# BBB_Headers.net
KiCad netlist of a schematic drawn in Altium Designer
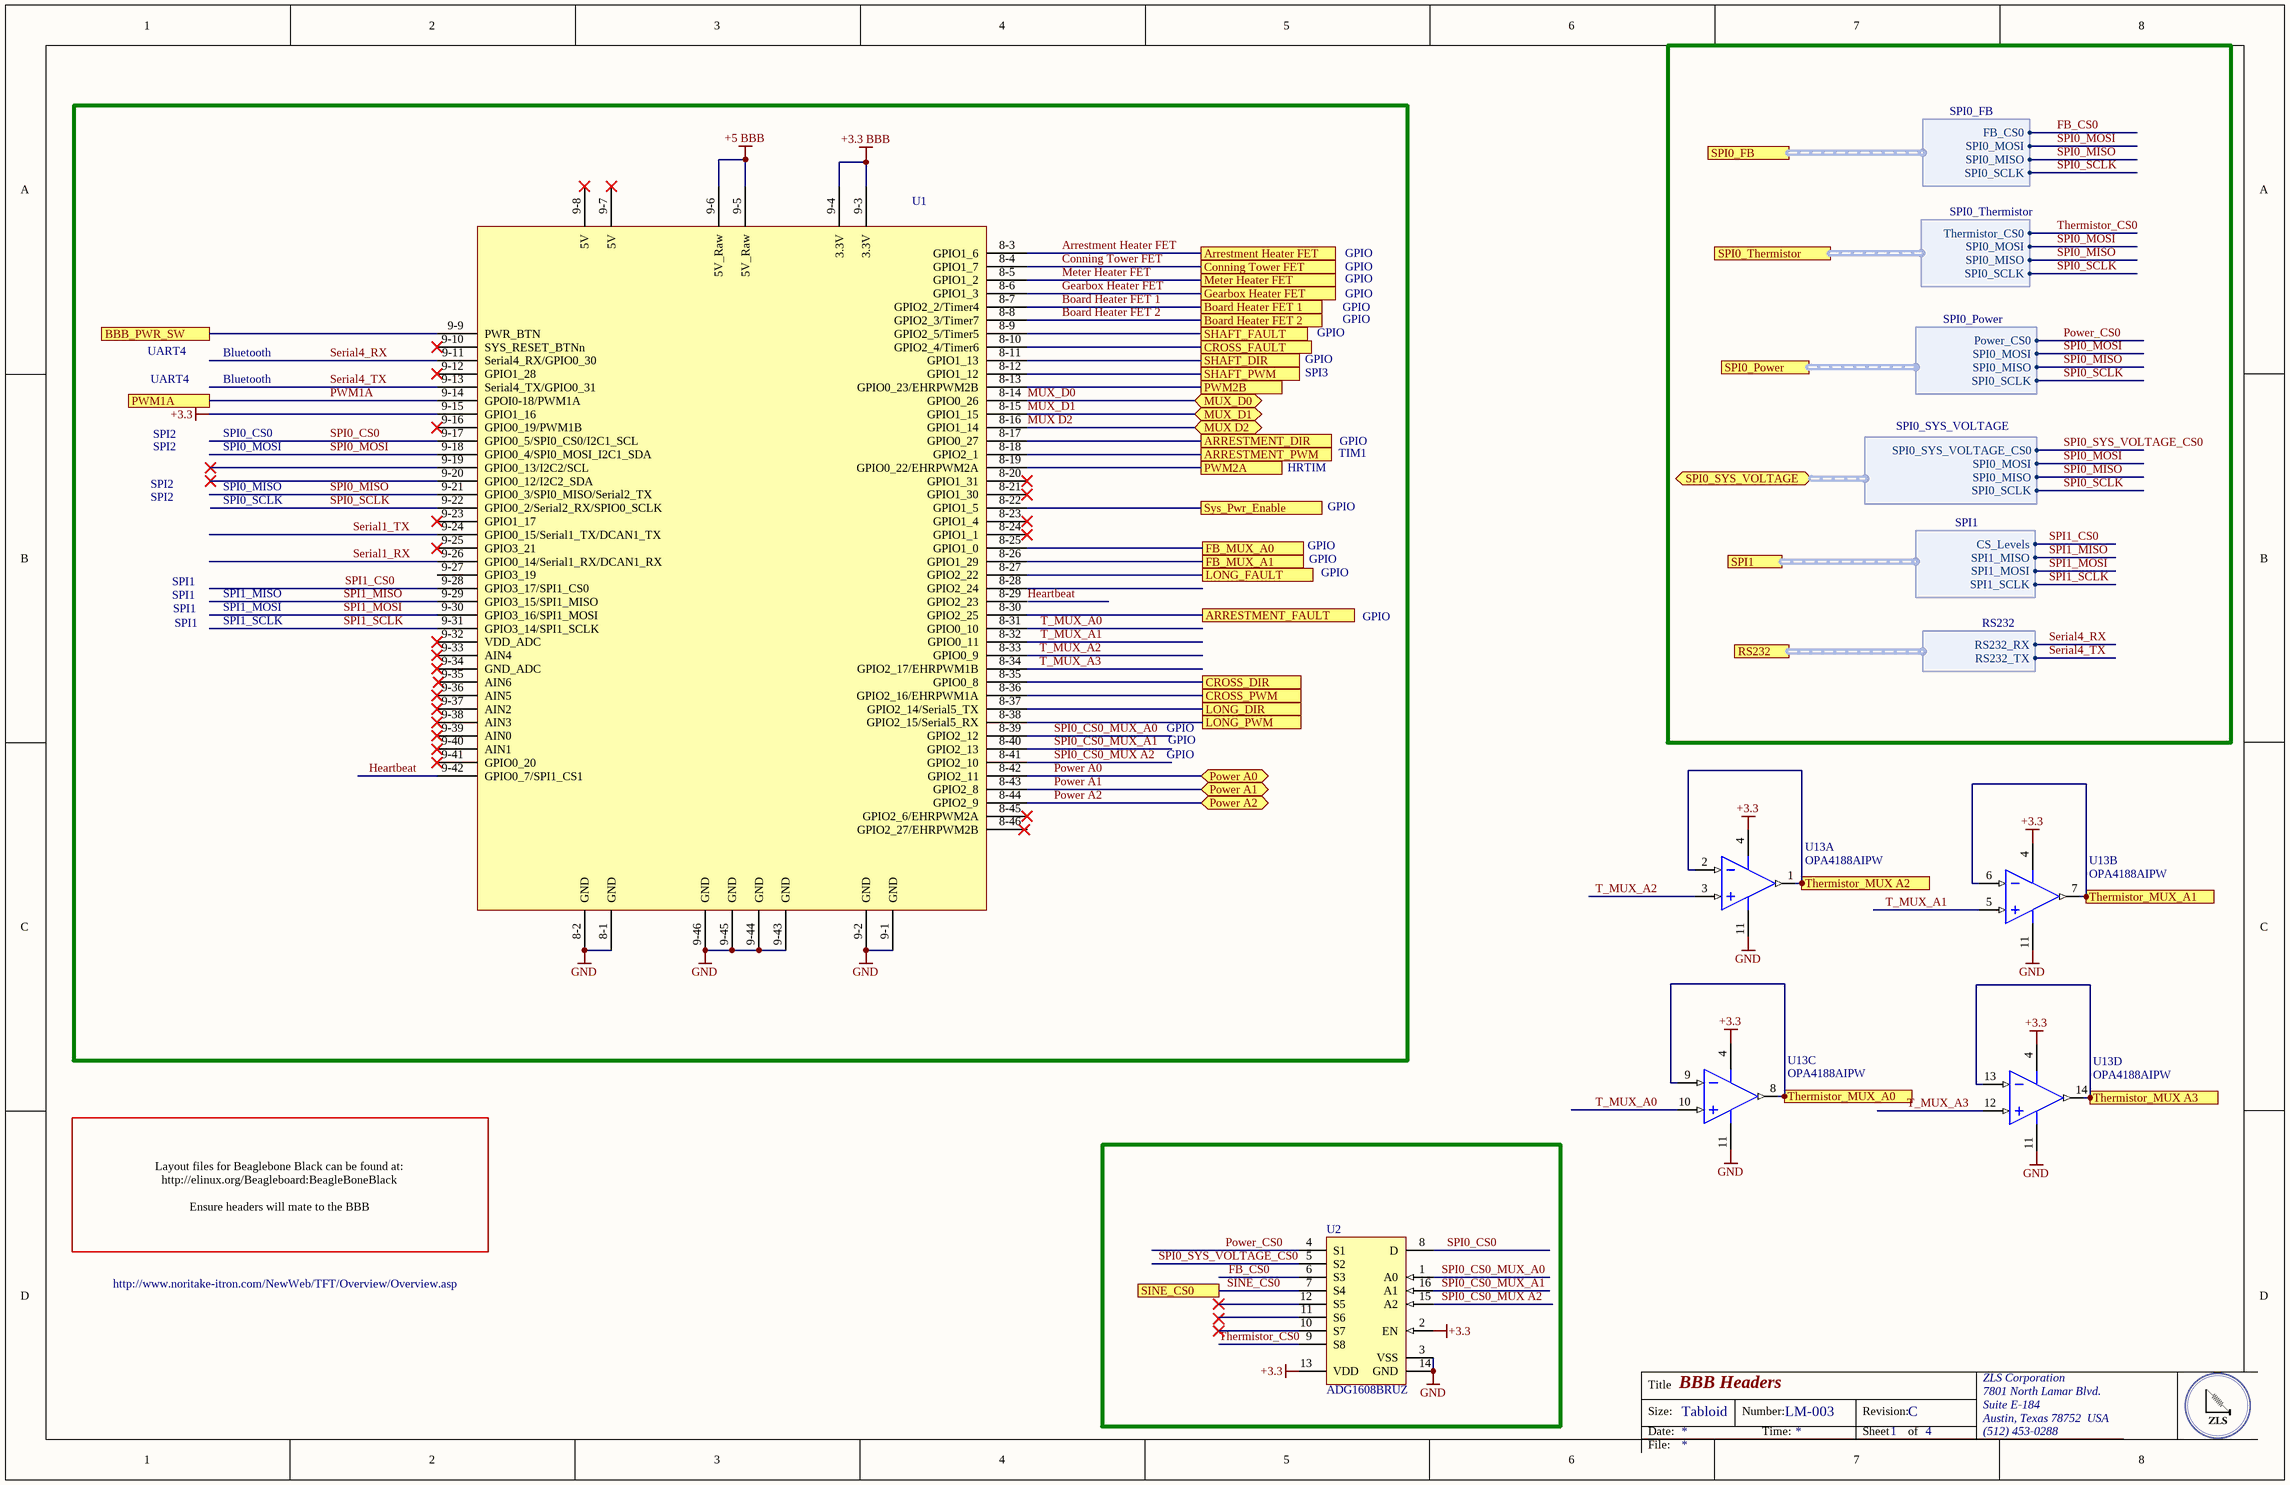
[diagram p0: BBB Headers.SchDoc]

(export (version "E")
  (design (tool "Eeschema 10.0.6"))
  (components
    (comp (ref "U1")
      (value "BBB Header x 2")
      (footprint "Beaglebone Black Thru")
      (description "Beaglebone Black Header")
      (fields
        (field (name "MANUFACTURER") "Samtec Inc.")
        (field (name "MANUFACTURER PART NUMBER") "SSW-123-03-G-D")
      )
      (libsource (lib "ZLS_Schematic_lib") (part "Beaglebone_Black"))
    )
    (comp (ref "U2")
      (value "ADG1608BRUZ")
      (footprint "ADI-RU-16_M")
      (description "4.5 Ohm Ron, 8-Channel +/-5 V,+12 V, +5 V and +3.3 V Multiplexer, 16-pin SOP (RU-16), Tube")
      (fields (field (name "MANUFACTURER") "Analog Devices Inc.") (field (name "BASE PART NUMBER") "ADG1608"))
      (libsource (lib "Altium Content Vault") (part "CMP-0793-00136-1"))
    )
    (comp (ref "U13")
      (value "OPA4188AIPW")
      (footprint "PW0014A_N")
      (fields (field (name "MANUFACTURER") "Texas Instruments"))
      (libsource (lib "Altium Content Vault") (part "TI-OPA4188-PW14"))
    )
  )
  (nets
    (net (code "7") (name "+3.3") (class "Default")
      (node (ref "U1") (pin "9-15") (pinfunction "GPIO1_16_9-15") (pintype "passive"))
      (node (ref "U13") (pin "4") (pinfunction "V+_4") (pintype "power_in"))
      (node (ref "U2") (pin "13") (pinfunction "VDD_13") (pintype "power_in"))
      (node (ref "U2") (pin "2") (pinfunction "EN_2") (pintype "input"))
    )
    (net (code "8") (name "+3.3 BBB") (class "Default")
      (node (ref "U1") (pin "9-3") (pinfunction "3.3V_9-3") (pintype "passive"))
      (node (ref "U1") (pin "9-4") (pinfunction "3.3V_9-4") (pintype "passive"))
    )
    (net (code "9") (name "+5 BBB") (class "Default")
      (node (ref "U1") (pin "9-5") (pinfunction "5V_Raw_9-5") (pintype "passive"))
      (node (ref "U1") (pin "9-6") (pinfunction "5V_Raw_9-6") (pintype "passive"))
    )
    (net (code "10") (name "/ARRESTMENT_DIR") (class "Default")
      (node (ref "U1") (pin "8-17") (pinfunction "GPIO0_27_8-17") (pintype "passive"))
    )
    (net (code "11") (name "/ARRESTMENT_FAULT") (class "Default")
      (node (ref "U1") (pin "8-30") (pinfunction "GPIO2_25_8-30") (pintype "passive"))
    )
    (net (code "12") (name "/ARRESTMENT_PWM") (class "Default")
      (node (ref "U1") (pin "8-18") (pinfunction "GPIO2_1_8-18") (pintype "passive"))
    )
    (net (code "13") (name "/Arrestment Heater FET") (class "Default")
      (node (ref "U1") (pin "8-3") (pinfunction "GPIO1_6_8-3") (pintype "passive"))
    )
    (net (code "14") (name "/BBB_PWR_SW") (class "Default")
      (node (ref "U1") (pin "9-9") (pinfunction "PWR_BTN_9-9") (pintype "passive"))
    )
    (net (code "15") (name "/Board Heater FET 1") (class "Default")
      (node (ref "U1") (pin "8-7") (pinfunction "GPIO2_2/Timer4_8-7") (pintype "passive"))
    )
    (net (code "16") (name "/Board Heater FET 2") (class "Default")
      (node (ref "U1") (pin "8-8") (pinfunction "GPIO2_3/Timer7_8-8") (pintype "passive"))
    )
    (net (code "17") (name "/CROSS_DIR") (class "Default")
      (node (ref "U1") (pin "8-35") (pinfunction "GPIO0_8_8-35") (pintype "passive"))
    )
    (net (code "18") (name "/CROSS_FAULT") (class "Default")
      (node (ref "U1") (pin "8-10") (pinfunction "GPIO2_4/Timer6_8-10") (pintype "passive"))
    )
    (net (code "19") (name "/CROSS_PWM") (class "Default")
      (node (ref "U1") (pin "8-36") (pinfunction "GPIO2_16/EHRPWM1A_8-36") (pintype "passive"))
    )
    (net (code "20") (name "/Conning Tower FET") (class "Default")
      (node (ref "U1") (pin "8-4") (pinfunction "GPIO1_7_8-4") (pintype "passive"))
    )
    (net (code "21") (name "/FB_CS0") (class "Default")
      (node (ref "U2") (pin "6") (pinfunction "S3_6") (pintype "passive"))
    )
    (net (code "22") (name "/FB_MUX_A0") (class "Default")
      (node (ref "U1") (pin "8-25") (pinfunction "GPIO1_0_8-25") (pintype "passive"))
    )
    (net (code "23") (name "/FB_MUX_A1") (class "Default")
      (node (ref "U1") (pin "8-26") (pinfunction "GPIO1_29_8-26") (pintype "passive"))
    )
    (net (code "24") (name "/Gearbox Heater FET") (class "Default")
      (node (ref "U1") (pin "8-6") (pinfunction "GPIO1_3_8-6") (pintype "passive"))
    )
    (net (code "25") (name "/Heartbeat") (class "Default")
      (node (ref "U1") (pin "8-29") (pinfunction "GPIO2_23_8-29") (pintype "passive"))
      (node (ref "U1") (pin "9-42") (pinfunction "GPIO0_7/SPI1_CS1_9-42") (pintype "passive"))
    )
    (net (code "26") (name "/LONG_DIR") (class "Default")
      (node (ref "U1") (pin "8-37") (pinfunction "GPIO2_14/Serial5_TX_8-37") (pintype "passive"))
    )
    (net (code "27") (name "/LONG_FAULT") (class "Default")
      (node (ref "U1") (pin "8-27") (pinfunction "GPIO2_22_8-27") (pintype "passive"))
    )
    (net (code "28") (name "/LONG_PWM") (class "Default")
      (node (ref "U1") (pin "8-38") (pinfunction "GPIO2_15/Serial5_RX_8-38") (pintype "passive"))
    )
    (net (code "29") (name "/MUX D2") (class "Default")
      (node (ref "U1") (pin "8-16") (pinfunction "GPIO1_14_8-16") (pintype "passive"))
    )
    (net (code "30") (name "/MUX_D0") (class "Default")
      (node (ref "U1") (pin "8-14") (pinfunction "GPIO0_26_8-14") (pintype "passive"))
    )
    (net (code "31") (name "/MUX_D1") (class "Default")
      (node (ref "U1") (pin "8-15") (pinfunction "GPIO1_15_8-15") (pintype "passive"))
    )
    (net (code "32") (name "/Meter Heater FET") (class "Default")
      (node (ref "U1") (pin "8-5") (pinfunction "GPIO1_2_8-5") (pintype "passive"))
    )
    (net (code "33") (name "/PWM1A") (class "Default")
      (node (ref "U1") (pin "9-14") (pinfunction "GPOI0-18/PWM1A_9-14") (pintype "passive"))
    )
    (net (code "34") (name "/PWM2A") (class "Default")
      (node (ref "U1") (pin "8-19") (pinfunction "GPIO0_22/EHRPWM2A_8-19") (pintype "passive"))
    )
    (net (code "35") (name "/PWM2B") (class "Default")
      (node (ref "U1") (pin "8-13") (pinfunction "GPIO0_23/EHRPWM2B_8-13") (pintype "passive"))
    )
    (net (code "36") (name "/Power A0") (class "Default")
      (node (ref "U1") (pin "8-42") (pinfunction "GPIO2_11_8-42") (pintype "passive"))
    )
    (net (code "37") (name "/Power A1") (class "Default")
      (node (ref "U1") (pin "8-43") (pinfunction "GPIO2_8_8-43") (pintype "passive"))
    )
    (net (code "38") (name "/Power A2") (class "Default")
      (node (ref "U1") (pin "8-44") (pinfunction "GPIO2_9_8-44") (pintype "passive"))
    )
    (net (code "39") (name "/Power_CS0") (class "Default")
      (node (ref "U2") (pin "4") (pinfunction "S1_4") (pintype "passive"))
    )
    (net (code "40") (name "/SHAFT_DIR") (class "Default")
      (node (ref "U1") (pin "8-11") (pinfunction "GPIO1_13_8-11") (pintype "passive"))
    )
    (net (code "41") (name "/SHAFT_FAULT") (class "Default")
      (node (ref "U1") (pin "8-9") (pinfunction "GPIO2_5/Timer5_8-9") (pintype "passive"))
    )
    (net (code "42") (name "/SHAFT_PWM") (class "Default")
      (node (ref "U1") (pin "8-12") (pinfunction "GPIO1_12_8-12") (pintype "passive"))
    )
    (net (code "43") (name "/SINE_CS0") (class "Default")
      (node (ref "U2") (pin "7") (pinfunction "S4_7") (pintype "passive"))
    )
    (net (code "44") (name "/SPI0_CS0") (class "Default")
      (node (ref "U1") (pin "9-17") (pinfunction "GPIO0_5/SPI0_CS0/I2C1_SCL_9-17") (pintype "passive"))
      (node (ref "U2") (pin "8") (pinfunction "D_8") (pintype "passive"))
    )
    (net (code "45") (name "/SPI0_CS0_MUX A2") (class "Default")
      (node (ref "U1") (pin "8-41") (pinfunction "GPIO2_10_8-41") (pintype "passive"))
      (node (ref "U2") (pin "15") (pinfunction "A2_15") (pintype "input"))
    )
    (net (code "46") (name "/SPI0_CS0_MUX_A0") (class "Default")
      (node (ref "U1") (pin "8-39") (pinfunction "GPIO2_12_8-39") (pintype "passive"))
      (node (ref "U2") (pin "1") (pinfunction "A0_1") (pintype "input"))
    )
    (net (code "47") (name "/SPI0_CS0_MUX_A1") (class "Default")
      (node (ref "U1") (pin "8-40") (pinfunction "GPIO2_13_8-40") (pintype "passive"))
      (node (ref "U2") (pin "16") (pinfunction "A1_16") (pintype "input"))
    )
    (net (code "48") (name "/SPI0_MISO") (class "Default")
      (node (ref "U1") (pin "9-21") (pinfunction "GPIO0_3/SPI0_MISO/Serial2_TX_9-21") (pintype "passive"))
    )
    (net (code "49") (name "/SPI0_MOSI") (class "Default")
      (node (ref "U1") (pin "9-18") (pinfunction "GPIO0_4/SPI0_MOSI_I2C1_SDA_9-18") (pintype "passive"))
    )
    (net (code "50") (name "/SPI0_SCLK") (class "Default")
      (node (ref "U1") (pin "9-22") (pinfunction "GPIO0_2/Serial2_RX/SPIO0_SCLK_9-22") (pintype "passive"))
    )
    (net (code "51") (name "/SPI0_SYS_VOLTAGE_CS0") (class "Default")
      (node (ref "U2") (pin "5") (pinfunction "S2_5") (pintype "passive"))
    )
    (net (code "52") (name "/SPI1_CS0") (class "Default")
      (node (ref "U1") (pin "9-28") (pinfunction "GPIO3_17/SPI1_CS0_9-28") (pintype "passive"))
    )
    (net (code "53") (name "/SPI1_MISO") (class "Default")
      (node (ref "U1") (pin "9-29") (pinfunction "GPIO3_15/SPI1_MISO_9-29") (pintype "passive"))
    )
    (net (code "54") (name "/SPI1_MOSI") (class "Default")
      (node (ref "U1") (pin "9-30") (pinfunction "GPIO3_16/SPI1_MOSI_9-30") (pintype "passive"))
    )
    (net (code "55") (name "/SPI1_SCLK") (class "Default")
      (node (ref "U1") (pin "9-31") (pinfunction "GPIO3_14/SPI1_SCLK_9-31") (pintype "passive"))
    )
    (net (code "56") (name "/Serial1_RX") (class "Default")
      (node (ref "U1") (pin "9-26") (pinfunction "GPIO0_14/Serial1_RX/DCAN1_RX_9-26") (pintype "passive"))
    )
    (net (code "57") (name "/Serial1_TX") (class "Default")
      (node (ref "U1") (pin "9-24") (pinfunction "GPIO0_15/Serial1_TX/DCAN1_TX_9-24") (pintype "passive"))
    )
    (net (code "58") (name "/Serial4_RX") (class "Default")
      (node (ref "U1") (pin "9-11") (pinfunction "Serial4_RX/GPIO0_30_9-11") (pintype "passive"))
    )
    (net (code "59") (name "/Serial4_TX") (class "Default")
      (node (ref "U1") (pin "9-13") (pinfunction "Serial4_TX/GPIO0_31_9-13") (pintype "passive"))
    )
    (net (code "60") (name "/Sys_Pwr_Enable") (class "Default")
      (node (ref "U1") (pin "8-22") (pinfunction "GPIO1_5_8-22") (pintype "passive"))
    )
    (net (code "61") (name "/T_MUX_A0") (class "Default")
      (node (ref "U1") (pin "8-31") (pinfunction "GPIO0_10_8-31") (pintype "passive"))
      (node (ref "U13") (pin "10") (pinfunction "IN_C+_10") (pintype "input"))
    )
    (net (code "62") (name "/T_MUX_A1") (class "Default")
      (node (ref "U1") (pin "8-32") (pinfunction "GPIO0_11_8-32") (pintype "passive"))
      (node (ref "U13") (pin "5") (pinfunction "IN_B+_5") (pintype "input"))
    )
    (net (code "63") (name "/T_MUX_A2") (class "Default")
      (node (ref "U1") (pin "8-33") (pinfunction "GPIO0_9_8-33") (pintype "passive"))
      (node (ref "U13") (pin "3") (pinfunction "IN_A+_3") (pintype "input"))
    )
    (net (code "64") (name "/T_MUX_A3") (class "Default")
      (node (ref "U1") (pin "8-34") (pinfunction "GPIO2_17/EHRPWM1B_8-34") (pintype "passive"))
      (node (ref "U13") (pin "12") (pinfunction "IN_D+_12") (pintype "input"))
    )
    (net (code "65") (name "/Thermistor_CS0") (class "Default")
      (node (ref "U2") (pin "9") (pinfunction "S8_9") (pintype "passive"))
    )
    (net (code "66") (name "/Thermistor_MUX A2") (class "Default")
      (node (ref "U13") (pin "1") (pinfunction "OUT_A_1") (pintype "output"))
      (node (ref "U13") (pin "2") (pinfunction "IN_A-_2") (pintype "input"))
    )
    (net (code "67") (name "/Thermistor_MUX A3") (class "Default")
      (node (ref "U13") (pin "13") (pinfunction "IN_D-_13") (pintype "input"))
      (node (ref "U13") (pin "14") (pinfunction "OUT_D_14") (pintype "output"))
    )
    (net (code "68") (name "/Thermistor_MUX_A0") (class "Default")
      (node (ref "U13") (pin "8") (pinfunction "OUT_C_8") (pintype "output"))
      (node (ref "U13") (pin "9") (pinfunction "IN_C-_9") (pintype "input"))
    )
    (net (code "69") (name "/Thermistor_MUX_A1") (class "Default")
      (node (ref "U13") (pin "6") (pinfunction "IN_B-_6") (pintype "input"))
      (node (ref "U13") (pin "7") (pinfunction "OUT_B_7") (pintype "output"))
    )
    (net (code "76") (name "GND") (class "Default")
      (node (ref "U1") (pin "8-1") (pinfunction "GND_8-1") (pintype "passive"))
      (node (ref "U1") (pin "8-2") (pinfunction "GND_8-2") (pintype "passive"))
      (node (ref "U1") (pin "9-1") (pinfunction "GND_9-1") (pintype "passive"))
      (node (ref "U1") (pin "9-2") (pinfunction "GND_9-2") (pintype "passive"))
      (node (ref "U1") (pin "9-43") (pinfunction "GND_9-43") (pintype "passive"))
      (node (ref "U1") (pin "9-44") (pinfunction "GND_9-44") (pintype "passive"))
      (node (ref "U1") (pin "9-45") (pinfunction "GND_9-45") (pintype "passive"))
      (node (ref "U1") (pin "9-46") (pinfunction "GND_9-46") (pintype "passive"))
      (node (ref "U13") (pin "11") (pinfunction "V-_11") (pintype "power_in"))
      (node (ref "U2") (pin "14") (pinfunction "GND_14") (pintype "power_in"))
      (node (ref "U2") (pin "3") (pinfunction "VSS_3") (pintype "power_in"))
    )
    (net (code "77") (name "unconnected-(U1-5V-Pad9-7)") (class "Default")
      (node (ref "U1") (pin "9-7") (pinfunction "5V_9-7") (pintype "passive+no_connect"))
    )
    (net (code "78") (name "unconnected-(U1-5V-Pad9-8)") (class "Default")
      (node (ref "U1") (pin "9-8") (pinfunction "5V_9-8") (pintype "passive+no_connect"))
    )
    (net (code "79") (name "unconnected-(U1-AIN0-Pad9-39)") (class "Default")
      (node (ref "U1") (pin "9-39") (pinfunction "AIN0_9-39") (pintype "passive+no_connect"))
    )
    (net (code "80") (name "unconnected-(U1-AIN1-Pad9-40)") (class "Default")
      (node (ref "U1") (pin "9-40") (pinfunction "AIN1_9-40") (pintype "passive+no_connect"))
    )
    (net (code "81") (name "unconnected-(U1-AIN2-Pad9-37)") (class "Default")
      (node (ref "U1") (pin "9-37") (pinfunction "AIN2_9-37") (pintype "passive+no_connect"))
    )
    (net (code "82") (name "unconnected-(U1-AIN3-Pad9-38)") (class "Default")
      (node (ref "U1") (pin "9-38") (pinfunction "AIN3_9-38") (pintype "passive+no_connect"))
    )
    (net (code "83") (name "unconnected-(U1-AIN4-Pad9-33)") (class "Default")
      (node (ref "U1") (pin "9-33") (pinfunction "AIN4_9-33") (pintype "passive+no_connect"))
    )
    (net (code "84") (name "unconnected-(U1-AIN5-Pad9-36)") (class "Default")
      (node (ref "U1") (pin "9-36") (pinfunction "AIN5_9-36") (pintype "passive+no_connect"))
    )
    (net (code "85") (name "unconnected-(U1-AIN6-Pad9-35)") (class "Default")
      (node (ref "U1") (pin "9-35") (pinfunction "AIN6_9-35") (pintype "passive"))
    )
    (net (code "86") (name "unconnected-(U1-GND_ADC-Pad9-34)") (class "Default")
      (node (ref "U1") (pin "9-34") (pinfunction "GND_ADC_9-34") (pintype "passive+no_connect"))
    )
    (net (code "87") (name "unconnected-(U1-GPIO0_12{slash}I2C2_SDA-Pad9-20)") (class "Default")
      (node (ref "U1") (pin "9-20") (pinfunction "GPIO0_12/I2C2_SDA_9-20") (pintype "passive+no_connect"))
    )
    (net (code "88") (name "unconnected-(U1-GPIO0_13{slash}I2C2{slash}SCL-Pad9-19)") (class "Default")
      (node (ref "U1") (pin "9-19") (pinfunction "GPIO0_13/I2C2/SCL_9-19") (pintype "passive+no_connect"))
    )
    (net (code "89") (name "unconnected-(U1-GPIO0_19{slash}PWM1B-Pad9-16)") (class "Default")
      (node (ref "U1") (pin "9-16") (pinfunction "GPIO0_19/PWM1B_9-16") (pintype "passive+no_connect"))
    )
    (net (code "90") (name "unconnected-(U1-GPIO0_20-Pad9-41)") (class "Default")
      (node (ref "U1") (pin "9-41") (pinfunction "GPIO0_20_9-41") (pintype "passive+no_connect"))
    )
    (net (code "91") (name "unconnected-(U1-GPIO1_1-Pad8-24)") (class "Default")
      (node (ref "U1") (pin "8-24") (pinfunction "GPIO1_1_8-24") (pintype "passive+no_connect"))
    )
    (net (code "92") (name "unconnected-(U1-GPIO1_4-Pad8-23)") (class "Default")
      (node (ref "U1") (pin "8-23") (pinfunction "GPIO1_4_8-23") (pintype "passive+no_connect"))
    )
    (net (code "93") (name "unconnected-(U1-GPIO1_17-Pad9-23)") (class "Default")
      (node (ref "U1") (pin "9-23") (pinfunction "GPIO1_17_9-23") (pintype "passive+no_connect"))
    )
    (net (code "94") (name "unconnected-(U1-GPIO1_28-Pad9-12)") (class "Default")
      (node (ref "U1") (pin "9-12") (pinfunction "GPIO1_28_9-12") (pintype "passive+no_connect"))
    )
    (net (code "95") (name "unconnected-(U1-GPIO1_30-Pad8-21)") (class "Default")
      (node (ref "U1") (pin "8-21") (pinfunction "GPIO1_30_8-21") (pintype "passive+no_connect"))
    )
    (net (code "96") (name "unconnected-(U1-GPIO1_31-Pad8-20)") (class "Default")
      (node (ref "U1") (pin "8-20") (pinfunction "GPIO1_31_8-20") (pintype "passive+no_connect"))
    )
    (net (code "97") (name "unconnected-(U1-GPIO2_6{slash}EHRPWM2A-Pad8-45)") (class "Default")
      (node (ref "U1") (pin "8-45") (pinfunction "GPIO2_6/EHRPWM2A_8-45") (pintype "passive+no_connect"))
    )
    (net (code "98") (name "unconnected-(U1-GPIO2_24-Pad8-28)") (class "Default")
      (node (ref "U1") (pin "8-28") (pinfunction "GPIO2_24_8-28") (pintype "passive"))
    )
    (net (code "99") (name "unconnected-(U1-GPIO2_27{slash}EHRPWM2B-Pad8-46)") (class "Default")
      (node (ref "U1") (pin "8-46") (pinfunction "GPIO2_27/EHRPWM2B_8-46") (pintype "passive"))
    )
    (net (code "100") (name "unconnected-(U1-GPIO3_19-Pad9-27)") (class "Default")
      (node (ref "U1") (pin "9-27") (pinfunction "GPIO3_19_9-27") (pintype "passive"))
    )
    (net (code "101") (name "unconnected-(U1-GPIO3_21-Pad9-25)") (class "Default")
      (node (ref "U1") (pin "9-25") (pinfunction "GPIO3_21_9-25") (pintype "passive+no_connect"))
    )
    (net (code "102") (name "unconnected-(U1-SYS_RESET_BTNn-Pad9-10)") (class "Default")
      (node (ref "U1") (pin "9-10") (pinfunction "SYS_RESET_BTNn_9-10") (pintype "passive+no_connect"))
    )
    (net (code "103") (name "unconnected-(U1-VDD_ADC-Pad9-32)") (class "Default")
      (node (ref "U1") (pin "9-32") (pinfunction "VDD_ADC_9-32") (pintype "passive+no_connect"))
    )
    (net (code "104") (name "unconnected-(U2-S5-Pad12)") (class "Default")
      (node (ref "U2") (pin "12") (pinfunction "S5_12") (pintype "passive+no_connect"))
    )
    (net (code "105") (name "unconnected-(U2-S6-Pad11)") (class "Default")
      (node (ref "U2") (pin "11") (pinfunction "S6_11") (pintype "passive"))
    )
    (net (code "106") (name "unconnected-(U2-S7-Pad10)") (class "Default")
      (node (ref "U2") (pin "10") (pinfunction "S7_10") (pintype "passive+no_connect"))
    )
  )
)
